# CurrentDriver.net
KiCad netlist of a schematic drawn in Altium Designer
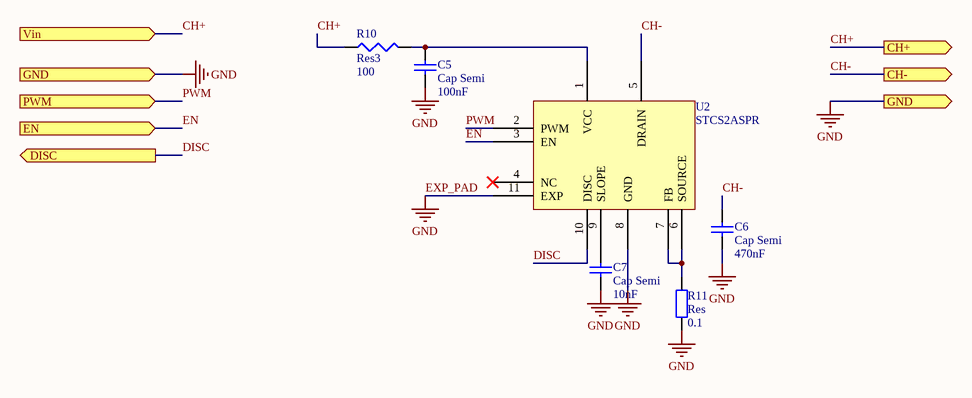
[diagram p0: CurrentDriver.SchDoc]

(export (version "E")
  (design (tool "Eeschema 10.0.6"))
  (components
    (comp (ref "C5")
      (value "Cap Semi")
      (footprint "1608[0603]")
      (description "Capacitor (Semiconductor SIM Model)")
      (fields (field (name "ALTIUM_VALUE") "100nF") (field (name "PUBLISHER") "Altium Limited"))
      (libsource (lib "Miscellaneous Devices") (part "Cap Semi"))
    )
    (comp (ref "C6")
      (value "Cap Semi")
      (footprint "1608[0603]")
      (description "Capacitor (Semiconductor SIM Model)")
      (fields (field (name "ALTIUM_VALUE") "470nF") (field (name "PUBLISHER") "Altium Limited"))
      (libsource (lib "Miscellaneous Devices") (part "Cap Semi"))
    )
    (comp (ref "C7")
      (value "Cap Semi")
      (footprint "1608[0603]")
      (description "Capacitor (Semiconductor SIM Model)")
      (fields (field (name "ALTIUM_VALUE") "10nF") (field (name "PUBLISHER") "Altium Limited"))
      (libsource (lib "Miscellaneous Devices") (part "Cap Semi"))
    )
    (comp (ref "R10")
      (value "Res3")
      (footprint "J1-0603")
      (description "Resistor")
      (fields (field (name "ALTIUM_VALUE") "100") (field (name "PUBLISHER") "Altium Limited"))
      (libsource (lib "Miscellaneous Devices") (part "Res3"))
    )
    (comp (ref "R11")
      (value "Res")
      (footprint "2512")
      (description "Generic resistor")
      (fields (field (name "ALTIUM_VALUE") "0.1"))
      (libsource (lib "ASI-LIB") (part "Res"))
    )
    (comp (ref "U2")
      (value "STCS2ASPR")
      (footprint "PowerSO-10")
      (description "LED CURRENT DRIVER")
      (libsource (lib "ASI-LIB") (part "STCS2A"))
    )
  )
  (nets
    (net (code "1") (name "/CH+") (class "Default")
      (node (ref "R10") (pin "2") (pinfunction "2_2") (pintype "passive"))
    )
    (net (code "2") (name "/CH-") (class "Default")
      (node (ref "C6") (pin "1") (pinfunction "1_1") (pintype "passive"))
      (node (ref "U2") (pin "5") (pinfunction "DRAIN_5") (pintype "passive"))
    )
    (net (code "3") (name "/DISC") (class "Default")
      (node (ref "U2") (pin "10") (pinfunction "DISC_10") (pintype "passive"))
    )
    (net (code "4") (name "/EN") (class "Default")
      (node (ref "U2") (pin "3") (pinfunction "EN_3") (pintype "passive"))
    )
    (net (code "5") (name "/PWM") (class "Default")
      (node (ref "U2") (pin "2") (pinfunction "PWM_2") (pintype "passive"))
    )
    (net (code "6") (name "GND") (class "Default")
      (node (ref "C5") (pin "2") (pinfunction "2_2") (pintype "passive"))
      (node (ref "C6") (pin "2") (pinfunction "2_2") (pintype "passive"))
      (node (ref "C7") (pin "2") (pinfunction "2_2") (pintype "passive"))
      (node (ref "R11") (pin "1") (pinfunction "1_1") (pintype "passive"))
      (node (ref "U2") (pin "11") (pinfunction "EXP_11") (pintype "passive"))
      (node (ref "U2") (pin "8") (pinfunction "GND_8") (pintype "passive"))
    )
    (net (code "7") (name "Net-(U2-FB)") (class "Default")
      (node (ref "R11") (pin "2") (pinfunction "2_2") (pintype "passive"))
      (node (ref "U2") (pin "6") (pinfunction "SOURCE_6") (pintype "passive"))
      (node (ref "U2") (pin "7") (pinfunction "FB_7") (pintype "passive"))
    )
    (net (code "8") (name "Net-(U2-SLOPE)") (class "Default")
      (node (ref "C7") (pin "1") (pinfunction "1_1") (pintype "passive"))
      (node (ref "U2") (pin "9") (pinfunction "SLOPE_9") (pintype "passive"))
    )
    (net (code "9") (name "Net-(U2-VCC)") (class "Default")
      (node (ref "C5") (pin "1") (pinfunction "1_1") (pintype "passive"))
      (node (ref "R10") (pin "1") (pinfunction "1_1") (pintype "passive"))
      (node (ref "U2") (pin "1") (pinfunction "VCC_1") (pintype "passive"))
    )
    (net (code "10") (name "unconnected-(U2-NC-Pad4)") (class "Default")
      (node (ref "U2") (pin "4") (pinfunction "NC_4") (pintype "passive+no_connect"))
    )
  )
)
